# Sheet2.net
KiCad netlist of a schematic drawn in Altium Designer
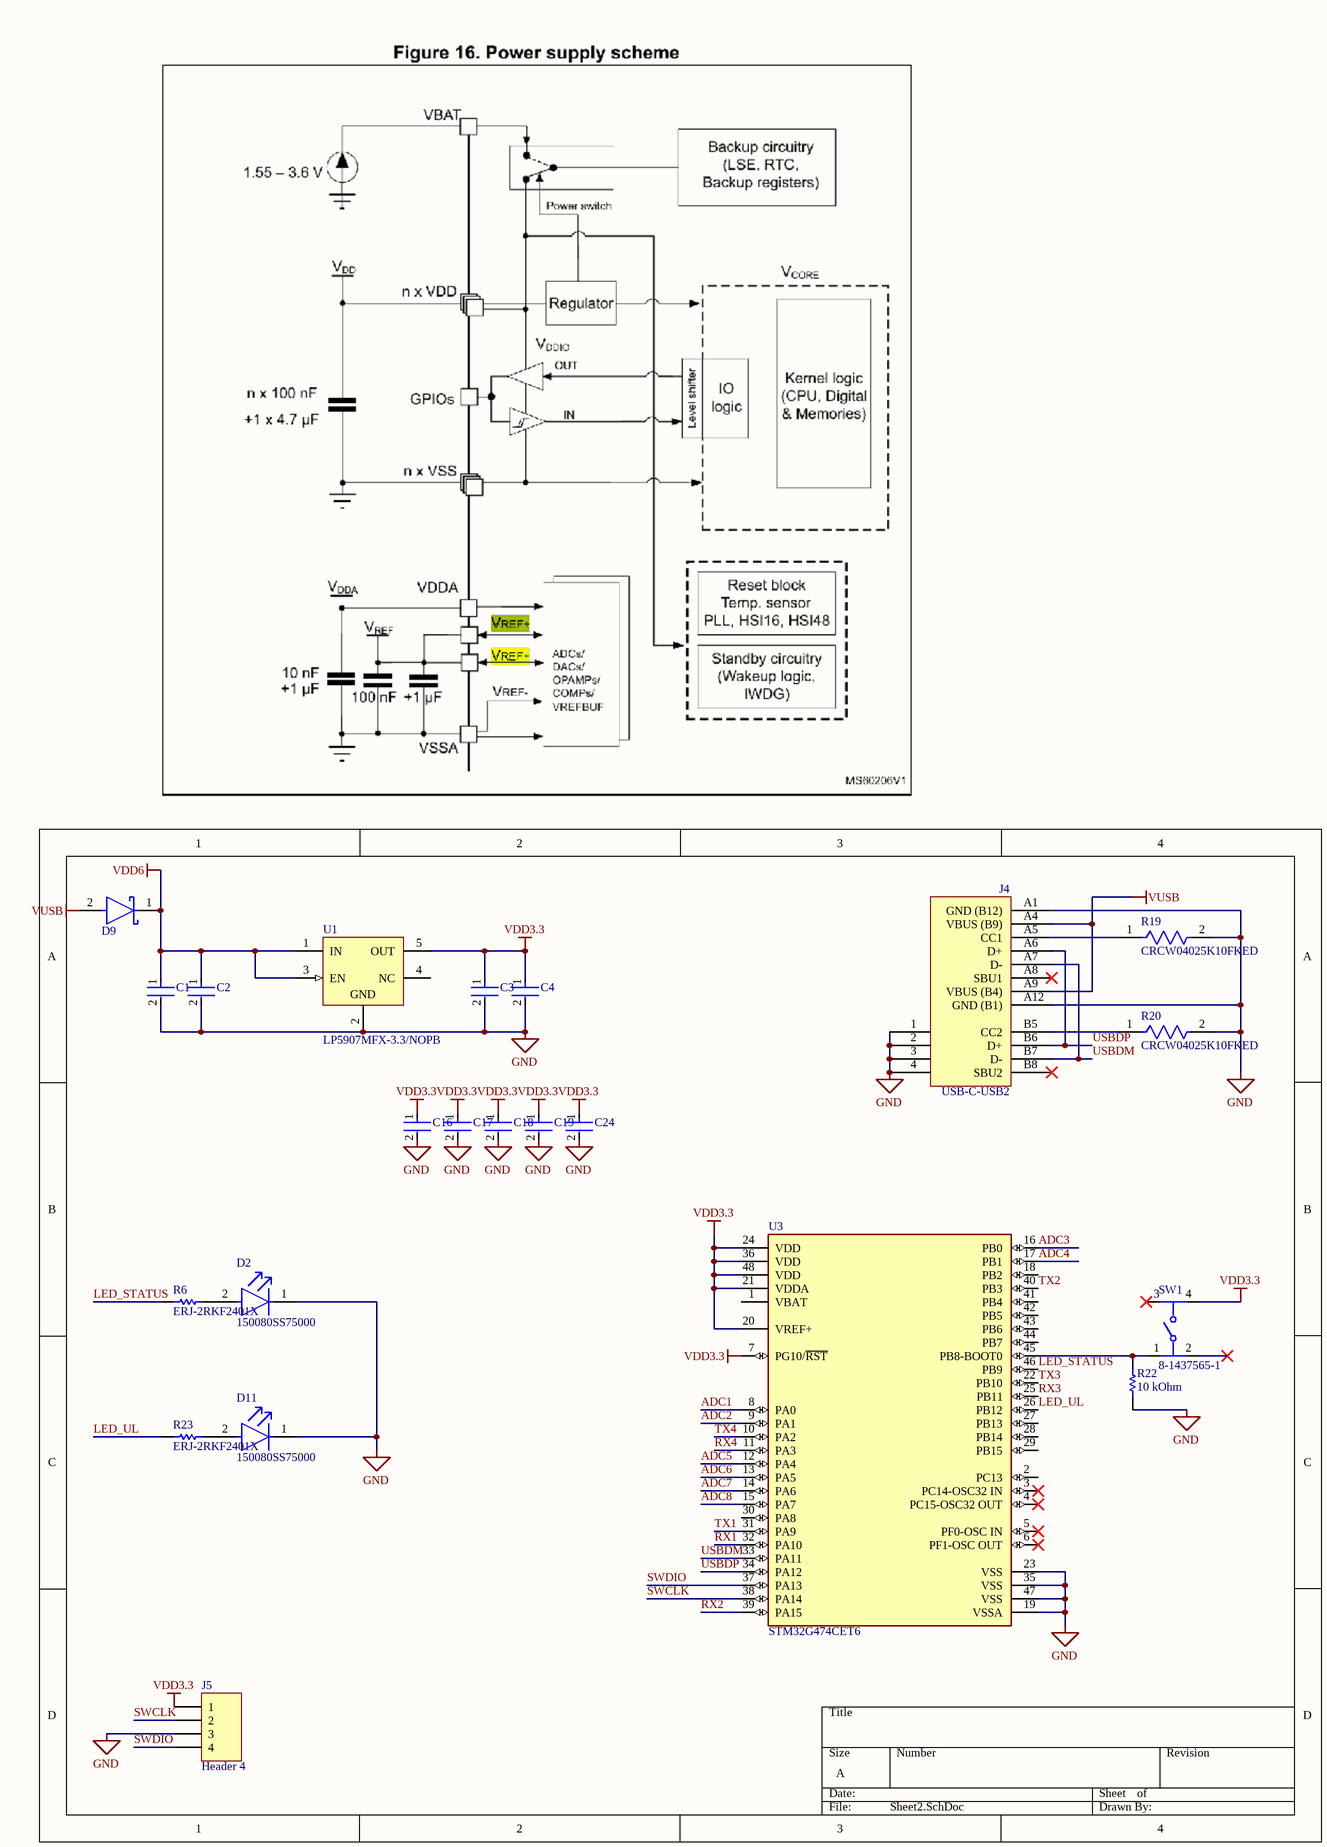
[diagram p0: Sheet2.SchDoc]

(export (version "E")
  (design (tool "Eeschema 10.0.6"))
  (components
    (comp (ref "C1")
      (value "C0603C225K4PACTU")
      (footprint "FP-C0603C225K4PACTU-MFG")
      (description "CAP CER 2.2UF 16V X5R 0603")
      (fields (field (name "TOLERANCE") "10%") (field (name "VOLTAGE") "16V"))
      (libsource (lib "Altium Content Vault") (part "b4654b650e69147ec39a6b967a45e02"))
    )
    (comp (ref "C2")
      (value "C0603C225K4PACTU")
      (footprint "FP-C0603C225K4PACTU-MFG")
      (description "CAP CER 2.2UF 16V X5R 0603")
      (fields (field (name "TOLERANCE") "10%") (field (name "VOLTAGE") "16V"))
      (libsource (lib "Altium Content Vault") (part "b4654b650e69147ec39a6b967a45e02"))
    )
    (comp (ref "C3")
      (value "C0603C225K4PACTU")
      (footprint "FP-C0603C225K4PACTU-MFG")
      (description "CAP CER 2.2UF 16V X5R 0603")
      (fields (field (name "TOLERANCE") "10%") (field (name "VOLTAGE") "16V"))
      (libsource (lib "Altium Content Vault") (part "b4654b650e69147ec39a6b967a45e02"))
    )
    (comp (ref "C4")
      (value "C0603C225K4PACTU")
      (footprint "FP-C0603C225K4PACTU-MFG")
      (description "CAP CER 2.2UF 16V X5R 0603")
      (fields (field (name "TOLERANCE") "10%") (field (name "VOLTAGE") "16V"))
      (libsource (lib "Altium Content Vault") (part "b4654b650e69147ec39a6b967a45e02"))
    )
    (comp (ref "C16")
      (value "C0603C225K4PACTU")
      (footprint "FP-C0603C225K4PACTU-MFG")
      (description "CAP CER 2.2UF 16V X5R 0603")
      (fields (field (name "TOLERANCE") "10%") (field (name "VOLTAGE") "16V"))
      (libsource (lib "Altium Content Vault") (part "b4654b650e69147ec39a6b967a45e02"))
    )
    (comp (ref "C17")
      (value "C0603C225K4PACTU")
      (footprint "FP-C0603C225K4PACTU-MFG")
      (description "CAP CER 2.2UF 16V X5R 0603")
      (fields (field (name "TOLERANCE") "10%") (field (name "VOLTAGE") "16V"))
      (libsource (lib "Altium Content Vault") (part "b4654b650e69147ec39a6b967a45e02"))
    )
    (comp (ref "C18")
      (value "C0603C225K4PACTU")
      (footprint "FP-C0603C225K4PACTU-MFG")
      (description "CAP CER 2.2UF 16V X5R 0603")
      (fields (field (name "TOLERANCE") "10%") (field (name "VOLTAGE") "16V"))
      (libsource (lib "Altium Content Vault") (part "b4654b650e69147ec39a6b967a45e02"))
    )
    (comp (ref "C19")
      (value "C0603C225K4PACTU")
      (footprint "FP-C0603C225K4PACTU-MFG")
      (description "CAP CER 2.2UF 16V X5R 0603")
      (fields (field (name "TOLERANCE") "10%") (field (name "VOLTAGE") "16V"))
      (libsource (lib "Altium Content Vault") (part "b4654b650e69147ec39a6b967a45e02"))
    )
    (comp (ref "C24")
      (value "C0603C225K4PACTU")
      (footprint "FP-C0603C225K4PACTU-MFG")
      (description "CAP CER 2.2UF 16V X5R 0603")
      (fields (field (name "TOLERANCE") "10%") (field (name "VOLTAGE") "16V"))
      (libsource (lib "Altium Content Vault") (part "b4654b650e69147ec39a6b967a45e02"))
    )
    (comp (ref "D2")
      (value "150080SS75000")
      (footprint "FP-150080SS75000-MFG")
      (description "LED RED CLEAR 0805 SMD")
      (libsource (lib "Altium Content Vault") (part "8706943c75ba83719d021d2fdc84c58"))
    )
    (comp (ref "D9")
      (value "VS-10MQ100NTRPBF")
      (footprint "FP-95400-MFG")
      (description "DIODE SCHOTTKY 100V 1A SMA")
      (fields
        (field (name "OCTOPART") "https://octopart.com/vs-10mq100ntrpbf-vishay-44340924")
        (field (name "MANUFACTURER") "Vishay")
      )
      (libsource (lib "Altium Content Vault") (part "c1678fac7984e62e0809fbf79c06691"))
    )
    (comp (ref "D11")
      (value "150080SS75000")
      (footprint "FP-150080SS75000-MFG")
      (description "LED RED CLEAR 0805 SMD")
      (libsource (lib "Altium Content Vault") (part "8706943c75ba83719d021d2fdc84c58"))
    )
    (comp (ref "J4")
      (value "USB-C-USB2")
      (footprint "USB-C-USB4105")
      (fields (field (name "MP") "USB4105") (field (name "MF") "Global Connector Technology"))
      (libsource (lib "dvrk-fixture") (part "USB-C-USB2"))
    )
    (comp (ref "J5")
      (value "Header 4")
      (footprint "HDR1X4")
      (description "Header, 4-Pin")
      (fields (field (name "PUBLISHER") "Altium Limited"))
      (libsource (lib "Miscellaneous Connectors") (part "Header 4"))
    )
    (comp (ref "R6")
      (value "ERJ-2RKF2401X")
      (footprint "RESC1005X40X25LL05T05")
      (fields (field (name "MANUFACTURER") "Panasonic"))
      (libsource (lib "Altium Content Vault") (part "RES"))
    )
    (comp (ref "R19")
      (value "CRCW04025K10FKED")
      (footprint "FP-CRCW0402-e3-IPC_C")
      (description "RES Thick Film, 5.1kΩ, 1%, 0.063W, 100ppm/°C, 0402")
      (fields (field (name "TOLERANCE") "1%"))
      (libsource (lib "Altium Content Vault") (part "1029c3af85768c4190bb7ad29bc67b5"))
    )
    (comp (ref "R20")
      (value "CRCW04025K10FKED")
      (footprint "FP-CRCW0402-e3-IPC_C")
      (description "RES Thick Film, 5.1kΩ, 1%, 0.063W, 100ppm/°C, 0402")
      (fields (field (name "TOLERANCE") "1%"))
      (libsource (lib "Altium Content Vault") (part "1029c3af85768c4190bb7ad29bc67b5"))
    )
    (comp (ref "R22")
      (value "10 kOhm")
      (footprint "RESC1005X40X25LL05T10")
      (fields (field (name "PART NUMBER") "RC0402FR-0710KL") (field (name "MANUFACTURER") "Yageo / Phycomp"))
      (libsource (lib "Altium Content Vault") (part "RES"))
    )
    (comp (ref "R23")
      (value "ERJ-2RKF2401X")
      (footprint "RESC1005X40X25LL05T05")
      (fields (field (name "MANUFACTURER") "Panasonic"))
      (libsource (lib "Altium Content Vault") (part "RES"))
    )
    (comp (ref "SW1")
      (value "8-1437565-1")
      (footprint "FP-8-1437565-1-MFG")
      (description "SWITCH TACTILE SPST-NO 0.02A 15V")
      (libsource (lib "Altium Content Vault") (part "b8895f3f4cefb76e1819d2863dba89b"))
    )
    (comp (ref "U1")
      (value "LP5907MFX-3.3/NOPB")
      (footprint "DBV0005A_N")
      (description "None")
      (libsource (lib "Altium Content Vault") (part "TI-LP5907-SOT-23-5"))
    )
    (comp (ref "U3")
      (value "STM32G474CET6")
      (footprint "FP-STM32G474CET6-MFG")
      (description "MAINSTREAM ARM CORTEX-M4 CORE WI")
      (fields
        (field (name "OCTOPART") "https://octopart.com/stm32g474cet6-stmicroelectronics-99072248")
        (field (name "MANUFACTURER") "STMicroelectronics")
      )
      (libsource (lib "Altium Content Vault") (part "96d063d3108c84c79c2ea684d87d0dc"))
    )
  )
  (nets
    (net (code "1") (name "/ADC1") (class "Default")
      (node (ref "U3") (pin "8") (pinfunction "PA0_8") (pintype "bidirectional"))
    )
    (net (code "2") (name "/ADC2") (class "Default")
      (node (ref "U3") (pin "9") (pinfunction "PA1_9") (pintype "bidirectional"))
    )
    (net (code "3") (name "/ADC3") (class "Default")
      (node (ref "U3") (pin "16") (pinfunction "PB0_16") (pintype "bidirectional"))
    )
    (net (code "4") (name "/ADC4") (class "Default")
      (node (ref "U3") (pin "17") (pinfunction "PB1_17") (pintype "bidirectional"))
    )
    (net (code "5") (name "/ADC5") (class "Default")
      (node (ref "U3") (pin "12") (pinfunction "PA4_12") (pintype "bidirectional"))
    )
    (net (code "6") (name "/ADC6") (class "Default")
      (node (ref "U3") (pin "13") (pinfunction "PA5_13") (pintype "bidirectional"))
    )
    (net (code "7") (name "/ADC7") (class "Default")
      (node (ref "U3") (pin "14") (pinfunction "PA6_14") (pintype "bidirectional"))
    )
    (net (code "8") (name "/ADC8") (class "Default")
      (node (ref "U3") (pin "15") (pinfunction "PA7_15") (pintype "bidirectional"))
    )
    (net (code "9") (name "/LED_STATUS") (class "Default")
      (node (ref "R6") (pin "1") (pinfunction "1_1") (pintype "passive"))
      (node (ref "U3") (pin "46") (pinfunction "PB9_46") (pintype "bidirectional"))
    )
    (net (code "10") (name "/LED_UL") (class "Default")
      (node (ref "R23") (pin "1") (pinfunction "1_1") (pintype "passive"))
      (node (ref "U3") (pin "26") (pinfunction "PB12_26") (pintype "bidirectional"))
    )
    (net (code "11") (name "/RX1") (class "Default")
      (node (ref "U3") (pin "32") (pinfunction "PA10_32") (pintype "bidirectional"))
    )
    (net (code "12") (name "/RX2") (class "Default")
      (node (ref "U3") (pin "39") (pinfunction "PA15_39") (pintype "bidirectional"))
    )
    (net (code "13") (name "/RX3") (class "Default")
      (node (ref "U3") (pin "25") (pinfunction "PB11_25") (pintype "bidirectional"))
    )
    (net (code "14") (name "/RX4") (class "Default")
      (node (ref "U3") (pin "11") (pinfunction "PA3_11") (pintype "bidirectional"))
    )
    (net (code "15") (name "/SWCLK") (class "Default")
      (node (ref "J5") (pin "2") (pinfunction "2_2") (pintype "passive"))
      (node (ref "U3") (pin "38") (pinfunction "PA14_38") (pintype "bidirectional"))
    )
    (net (code "16") (name "/SWDIO") (class "Default")
      (node (ref "J5") (pin "4") (pinfunction "4_4") (pintype "passive"))
      (node (ref "U3") (pin "37") (pinfunction "PA13_37") (pintype "bidirectional"))
    )
    (net (code "17") (name "/TX1") (class "Default")
      (node (ref "U3") (pin "31") (pinfunction "PA9_31") (pintype "bidirectional"))
    )
    (net (code "18") (name "/TX2") (class "Default")
      (node (ref "U3") (pin "40") (pinfunction "PB3_40") (pintype "bidirectional"))
    )
    (net (code "19") (name "/TX3") (class "Default")
      (node (ref "U3") (pin "22") (pinfunction "PB10_22") (pintype "bidirectional"))
    )
    (net (code "20") (name "/TX4") (class "Default")
      (node (ref "U3") (pin "10") (pinfunction "PA2_10") (pintype "bidirectional"))
    )
    (net (code "21") (name "/USBDM") (class "Default")
      (node (ref "J4") (pin "A7") (pinfunction "D-_A7") (pintype "passive"))
      (node (ref "J4") (pin "B7") (pinfunction "D-_B7") (pintype "passive"))
      (node (ref "U3") (pin "33") (pinfunction "PA11_33") (pintype "bidirectional"))
    )
    (net (code "22") (name "/USBDP") (class "Default")
      (node (ref "J4") (pin "A6") (pinfunction "D+_A6") (pintype "passive"))
      (node (ref "J4") (pin "B6") (pinfunction "D+_B6") (pintype "passive"))
      (node (ref "U3") (pin "34") (pinfunction "PA12_34") (pintype "bidirectional"))
    )
    (net (code "23") (name "GND") (class "Default")
      (node (ref "C1") (pin "2") (pinfunction "2_2") (pintype "passive"))
      (node (ref "C16") (pin "2") (pinfunction "2_2") (pintype "passive"))
      (node (ref "C17") (pin "2") (pinfunction "2_2") (pintype "passive"))
      (node (ref "C18") (pin "2") (pinfunction "2_2") (pintype "passive"))
      (node (ref "C19") (pin "2") (pinfunction "2_2") (pintype "passive"))
      (node (ref "C2") (pin "2") (pinfunction "2_2") (pintype "passive"))
      (node (ref "C24") (pin "2") (pinfunction "2_2") (pintype "passive"))
      (node (ref "C3") (pin "2") (pinfunction "2_2") (pintype "passive"))
      (node (ref "C4") (pin "2") (pinfunction "2_2") (pintype "passive"))
      (node (ref "D11") (pin "1") (pinfunction "C_1") (pintype "passive"))
      (node (ref "D2") (pin "1") (pinfunction "C_1") (pintype "passive"))
      (node (ref "J4") (pin "1") (pinfunction "CHASIS_1") (pintype "power_in"))
      (node (ref "J4") (pin "2") (pinfunction "CHASIS_2") (pintype "power_in"))
      (node (ref "J4") (pin "3") (pinfunction "CHASIS_3") (pintype "power_in"))
      (node (ref "J4") (pin "4") (pinfunction "CHASIS_4") (pintype "power_in"))
      (node (ref "J4") (pin "A1") (pinfunction "GND_(B12)_A1") (pintype "passive"))
      (node (ref "J4") (pin "A12") (pinfunction "GND_(B1)_A12") (pintype "passive"))
      (node (ref "J5") (pin "3") (pinfunction "3_3") (pintype "passive"))
      (node (ref "R19") (pin "2") (pinfunction "2_2") (pintype "passive"))
      (node (ref "R20") (pin "2") (pinfunction "2_2") (pintype "passive"))
      (node (ref "R22") (pin "1") (pinfunction "1_1") (pintype "passive"))
      (node (ref "U1") (pin "2") (pinfunction "GND_2") (pintype "power_in"))
      (node (ref "U3") (pin "19") (pinfunction "VSSA_19") (pintype "power_in"))
      (node (ref "U3") (pin "23") (pinfunction "VSS_23") (pintype "power_in"))
      (node (ref "U3") (pin "35") (pinfunction "VSS_35") (pintype "power_in"))
      (node (ref "U3") (pin "47") (pinfunction "VSS_47") (pintype "power_in"))
    )
    (net (code "24") (name "Net-(D2-A)") (class "Default")
      (node (ref "D2") (pin "2") (pinfunction "A_2") (pintype "passive"))
      (node (ref "R6") (pin "2") (pinfunction "2_2") (pintype "passive"))
    )
    (net (code "25") (name "Net-(D11-A)") (class "Default")
      (node (ref "D11") (pin "2") (pinfunction "A_2") (pintype "passive"))
      (node (ref "R23") (pin "2") (pinfunction "2_2") (pintype "passive"))
    )
    (net (code "26") (name "Net-(J4-CC1)") (class "Default")
      (node (ref "J4") (pin "A5") (pinfunction "CC1_A5") (pintype "passive"))
      (node (ref "R19") (pin "1") (pinfunction "1_1") (pintype "passive"))
    )
    (net (code "27") (name "Net-(J4-CC2)") (class "Default")
      (node (ref "J4") (pin "B5") (pinfunction "CC2_B5") (pintype "passive"))
      (node (ref "R20") (pin "1") (pinfunction "1_1") (pintype "passive"))
    )
    (net (code "28") (name "Net-(U3-PB8-BOOT0)") (class "Default")
      (node (ref "R22") (pin "2") (pinfunction "2_2") (pintype "passive"))
      (node (ref "SW1") (pin "1") (pinfunction "1_1") (pintype "passive"))
      (node (ref "U3") (pin "45") (pinfunction "PB8-BOOT0_45") (pintype "bidirectional"))
    )
    (net (code "29") (name "VDD3.3") (class "Default")
      (node (ref "C16") (pin "1") (pinfunction "1_1") (pintype "passive"))
      (node (ref "C17") (pin "1") (pinfunction "1_1") (pintype "passive"))
      (node (ref "C18") (pin "1") (pinfunction "1_1") (pintype "passive"))
      (node (ref "C19") (pin "1") (pinfunction "1_1") (pintype "passive"))
      (node (ref "C24") (pin "1") (pinfunction "1_1") (pintype "passive"))
      (node (ref "C3") (pin "1") (pinfunction "1_1") (pintype "passive"))
      (node (ref "C4") (pin "1") (pinfunction "1_1") (pintype "passive"))
      (node (ref "J5") (pin "1") (pinfunction "1_1") (pintype "passive"))
      (node (ref "SW1") (pin "4") (pinfunction "4_4") (pintype "passive"))
      (node (ref "U1") (pin "5") (pinfunction "OUT_5") (pintype "power_in"))
      (node (ref "U3") (pin "20") (pinfunction "VREF+_20") (pintype "power_in"))
      (node (ref "U3") (pin "21") (pinfunction "VDDA_21") (pintype "power_in"))
      (node (ref "U3") (pin "24") (pinfunction "VDD_24") (pintype "power_in"))
      (node (ref "U3") (pin "36") (pinfunction "VDD_36") (pintype "power_in"))
      (node (ref "U3") (pin "48") (pinfunction "VDD_48") (pintype "power_in"))
      (node (ref "U3") (pin "7") (pinfunction "PG10/~{RST}_7") (pintype "bidirectional"))
    )
    (net (code "30") (name "VDD6") (class "Default")
      (node (ref "C1") (pin "1") (pinfunction "1_1") (pintype "passive"))
      (node (ref "C2") (pin "1") (pinfunction "1_1") (pintype "passive"))
      (node (ref "D9") (pin "1") (pinfunction "C_1") (pintype "passive"))
      (node (ref "U1") (pin "1") (pinfunction "IN_1") (pintype "power_in"))
      (node (ref "U1") (pin "3") (pinfunction "EN_3") (pintype "input"))
    )
    (net (code "31") (name "VUSB") (class "Default")
      (node (ref "D9") (pin "2") (pinfunction "A_2") (pintype "passive"))
      (node (ref "J4") (pin "A4") (pinfunction "VBUS_(B9)_A4") (pintype "passive"))
      (node (ref "J4") (pin "A9") (pinfunction "VBUS_(B4)_A9") (pintype "passive"))
    )
    (net (code "32") (name "unconnected-(J4-SBU1-PadA8)") (class "Default")
      (node (ref "J4") (pin "A8") (pinfunction "SBU1_A8") (pintype "passive+no_connect"))
    )
    (net (code "33") (name "unconnected-(J4-SBU2-PadB8)") (class "Default")
      (node (ref "J4") (pin "B8") (pinfunction "SBU2_B8") (pintype "passive+no_connect"))
    )
    (net (code "34") (name "unconnected-(SW1-Pad2)") (class "Default")
      (node (ref "SW1") (pin "2") (pinfunction "2_2") (pintype "passive+no_connect"))
    )
    (net (code "35") (name "unconnected-(SW1-Pad3)") (class "Default")
      (node (ref "SW1") (pin "3") (pinfunction "3_3") (pintype "passive+no_connect"))
    )
    (net (code "36") (name "unconnected-(U1-NC-Pad4)") (class "Default")
      (node (ref "U1") (pin "4") (pinfunction "NC_4") (pintype "passive"))
    )
    (net (code "37") (name "unconnected-(U3-PA8-Pad30)") (class "Default")
      (node (ref "U3") (pin "30") (pinfunction "PA8_30") (pintype "bidirectional"))
    )
    (net (code "38") (name "unconnected-(U3-PB2-Pad18)") (class "Default")
      (node (ref "U3") (pin "18") (pinfunction "PB2_18") (pintype "bidirectional"))
    )
    (net (code "39") (name "unconnected-(U3-PB4-Pad41)") (class "Default")
      (node (ref "U3") (pin "41") (pinfunction "PB4_41") (pintype "bidirectional"))
    )
    (net (code "40") (name "unconnected-(U3-PB5-Pad42)") (class "Default")
      (node (ref "U3") (pin "42") (pinfunction "PB5_42") (pintype "bidirectional"))
    )
    (net (code "41") (name "unconnected-(U3-PB6-Pad43)") (class "Default")
      (node (ref "U3") (pin "43") (pinfunction "PB6_43") (pintype "bidirectional"))
    )
    (net (code "42") (name "unconnected-(U3-PB7-Pad44)") (class "Default")
      (node (ref "U3") (pin "44") (pinfunction "PB7_44") (pintype "bidirectional"))
    )
    (net (code "43") (name "unconnected-(U3-PB13-Pad27)") (class "Default")
      (node (ref "U3") (pin "27") (pinfunction "PB13_27") (pintype "bidirectional"))
    )
    (net (code "44") (name "unconnected-(U3-PB14-Pad28)") (class "Default")
      (node (ref "U3") (pin "28") (pinfunction "PB14_28") (pintype "bidirectional"))
    )
    (net (code "45") (name "unconnected-(U3-PB15-Pad29)") (class "Default")
      (node (ref "U3") (pin "29") (pinfunction "PB15_29") (pintype "bidirectional"))
    )
    (net (code "46") (name "unconnected-(U3-PC13-Pad2)") (class "Default")
      (node (ref "U3") (pin "2") (pinfunction "PC13_2") (pintype "bidirectional"))
    )
    (net (code "47") (name "unconnected-(U3-PC14-OSC32_IN-Pad3)") (class "Default")
      (node (ref "U3") (pin "3") (pinfunction "PC14-OSC32_IN_3") (pintype "bidirectional+no_connect"))
    )
    (net (code "48") (name "unconnected-(U3-PC15-OSC32_OUT-Pad4)") (class "Default")
      (node (ref "U3") (pin "4") (pinfunction "PC15-OSC32_OUT_4") (pintype "bidirectional+no_connect"))
    )
    (net (code "49") (name "unconnected-(U3-PF0-OSC_IN-Pad5)") (class "Default")
      (node (ref "U3") (pin "5") (pinfunction "PF0-OSC_IN_5") (pintype "bidirectional+no_connect"))
    )
    (net (code "50") (name "unconnected-(U3-PF1-OSC_OUT-Pad6)") (class "Default")
      (node (ref "U3") (pin "6") (pinfunction "PF1-OSC_OUT_6") (pintype "bidirectional+no_connect"))
    )
    (net (code "51") (name "unconnected-(U3-VBAT-Pad1)") (class "Default")
      (node (ref "U3") (pin "1") (pinfunction "VBAT_1") (pintype "power_in"))
    )
  )
)
